# M169X.net
KiCad netlist of a schematic drawn in EAGLE
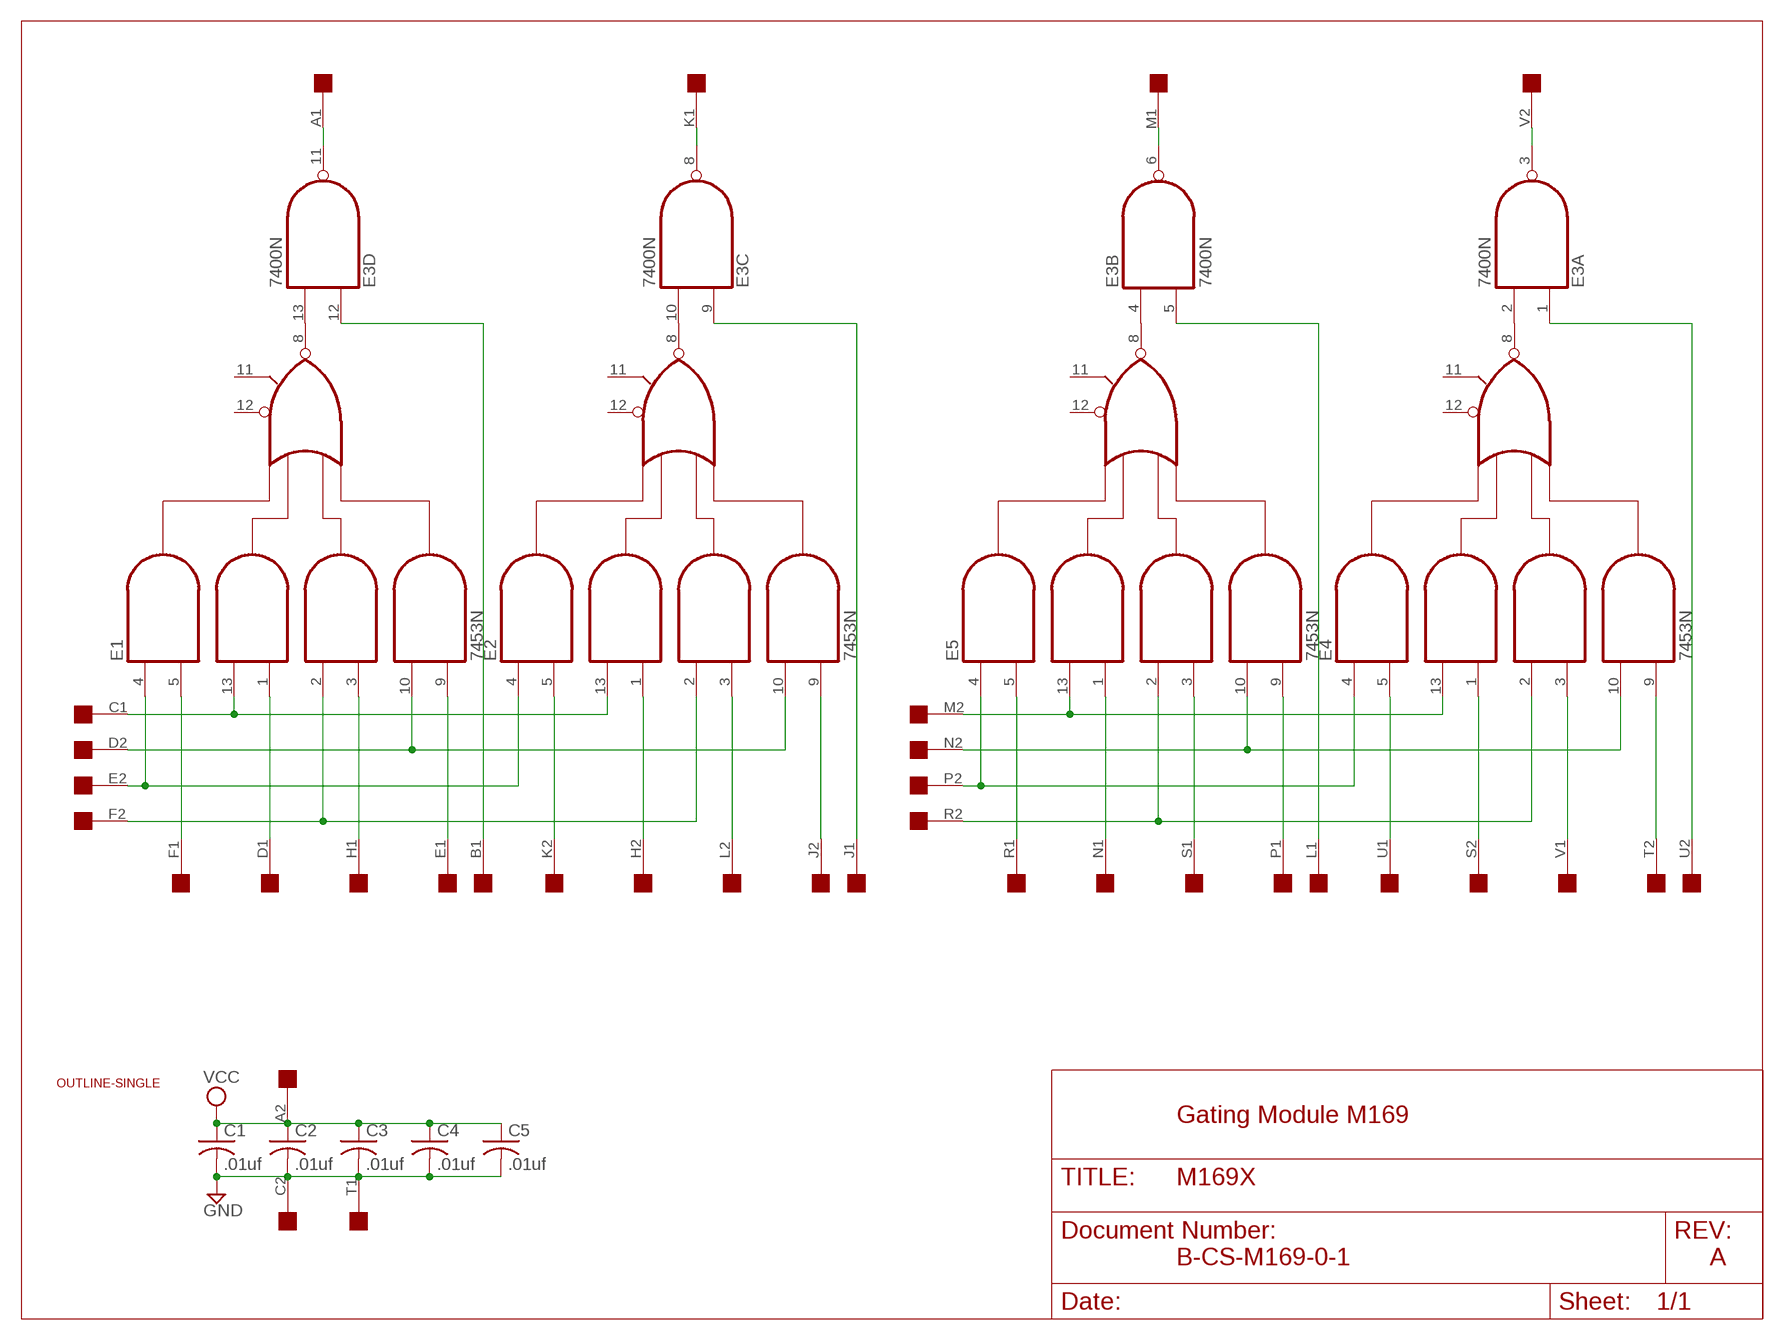
[diagram p0: schematic, sheet 1]

(export (version "E")
  (design (tool "Eeschema 10.0.6"))
  (components
    (comp (ref "C1")
      (value ".01uf")
      (footprint "eagle-import:C050-025X075")
      (libsource (lib "eagle-import") (part "C-US050-025X075"))
    )
    (comp (ref "C2")
      (value ".01uf")
      (footprint "eagle-import:C050-025X075")
      (libsource (lib "eagle-import") (part "C-US050-025X075"))
    )
    (comp (ref "C3")
      (value ".01uf")
      (footprint "eagle-import:C050-025X075")
      (libsource (lib "eagle-import") (part "C-US050-025X075"))
    )
    (comp (ref "C4")
      (value ".01uf")
      (footprint "eagle-import:C050-025X075")
      (libsource (lib "eagle-import") (part "C-US050-025X075"))
    )
    (comp (ref "C5")
      (value ".01uf")
      (footprint "eagle-import:C050-025X075")
      (libsource (lib "eagle-import") (part "C-US050-025X075"))
    )
    (comp (ref "E1")
      (value "7453N")
      (footprint "eagle-import:DIL14")
      (libsource (lib "eagle-import") (part "7453N"))
    )
    (comp (ref "E2")
      (value "7453N")
      (footprint "eagle-import:DIL14")
      (libsource (lib "eagle-import") (part "7453N"))
    )
    (comp (ref "E3")
      (value "7400N")
      (footprint "eagle-import:DIL14")
      (libsource (lib "eagle-import") (part "7400N"))
    )
    (comp (ref "E4")
      (value "7453N")
      (footprint "eagle-import:DIL14")
      (libsource (lib "eagle-import") (part "7453N"))
    )
    (comp (ref "E5")
      (value "7453N")
      (footprint "eagle-import:DIL14")
      (libsource (lib "eagle-import") (part "7453N"))
    )
    (comp (ref "U$1")
      (value "OUTLINE-SINGLE")
      (footprint "eagle-import:SINGLE")
      (libsource (lib "eagle-import") (part "OUTLINE-SINGLE"))
    )
    (comp (ref "U$2")
      (value "EDGE-2CONNECTOR")
      (footprint "eagle-import:EDGE-CON2")
      (libsource (lib "eagle-import") (part "EDGE-2CONNECTOR"))
    )
  )
  (nets
    (net (code "1") (name "GND") (class "Default")
      (node (ref "C1") (pin "2") (pinfunction "2_2") (pintype "passive"))
      (node (ref "C2") (pin "2") (pinfunction "2_2") (pintype "passive"))
      (node (ref "C3") (pin "2") (pinfunction "2_2") (pintype "passive"))
      (node (ref "C4") (pin "2") (pinfunction "2_2") (pintype "passive"))
      (node (ref "C5") (pin "2") (pinfunction "2_2") (pintype "passive"))
      (node (ref "U$2") (pin "C2") (pinfunction "1_C2") (pintype "bidirectional"))
      (node (ref "U$2") (pin "T1") (pinfunction "1_T1") (pintype "bidirectional"))
    )
    (net (code "2") (name "Net-(E1A-I1)") (class "Default")
      (node (ref "E1") (pin "4") (pinfunction "I1_4") (pintype "input"))
      (node (ref "E2") (pin "4") (pinfunction "I1_4") (pintype "input"))
      (node (ref "U$2") (pin "E2") (pinfunction "1_E2") (pintype "bidirectional"))
    )
    (net (code "3") (name "Net-(E1A-I2)") (class "Default")
      (node (ref "E1") (pin "5") (pinfunction "I2_5") (pintype "input"))
      (node (ref "U$2") (pin "F1") (pinfunction "1_F1") (pintype "bidirectional"))
    )
    (net (code "4") (name "Net-(E1A-I3)") (class "Default")
      (node (ref "E1") (pin "13") (pinfunction "I3_13") (pintype "input"))
      (node (ref "E2") (pin "13") (pinfunction "I3_13") (pintype "input"))
      (node (ref "U$2") (pin "C1") (pinfunction "1_C1") (pintype "bidirectional"))
    )
    (net (code "5") (name "Net-(E1A-I4)") (class "Default")
      (node (ref "E1") (pin "1") (pinfunction "I4_1") (pintype "input"))
      (node (ref "U$2") (pin "D1") (pinfunction "1_D1") (pintype "bidirectional"))
    )
    (net (code "6") (name "Net-(E1A-I5)") (class "Default")
      (node (ref "E1") (pin "2") (pinfunction "I5_2") (pintype "input"))
      (node (ref "E2") (pin "2") (pinfunction "I5_2") (pintype "input"))
      (node (ref "U$2") (pin "F2") (pinfunction "1_F2") (pintype "bidirectional"))
    )
    (net (code "7") (name "Net-(E1A-I6)") (class "Default")
      (node (ref "E1") (pin "3") (pinfunction "I6_3") (pintype "input"))
      (node (ref "U$2") (pin "H1") (pinfunction "1_H1") (pintype "bidirectional"))
    )
    (net (code "8") (name "Net-(E1A-I7)") (class "Default")
      (node (ref "E1") (pin "10") (pinfunction "I7_10") (pintype "input"))
      (node (ref "E2") (pin "10") (pinfunction "I7_10") (pintype "input"))
      (node (ref "U$2") (pin "D2") (pinfunction "1_D2") (pintype "bidirectional"))
    )
    (net (code "9") (name "Net-(E1A-I8)") (class "Default")
      (node (ref "E1") (pin "9") (pinfunction "I8_9") (pintype "input"))
      (node (ref "U$2") (pin "E1") (pinfunction "1_E1") (pintype "bidirectional"))
    )
    (net (code "10") (name "Net-(E1A-O)") (class "Default")
      (node (ref "E1") (pin "8") (pinfunction "O_8") (pintype "output"))
      (node (ref "E3") (pin "13") (pinfunction "I1_13") (pintype "input"))
    )
    (net (code "11") (name "Net-(E2A-I2)") (class "Default")
      (node (ref "E2") (pin "5") (pinfunction "I2_5") (pintype "input"))
      (node (ref "U$2") (pin "K2") (pinfunction "1_K2") (pintype "bidirectional"))
    )
    (net (code "12") (name "Net-(E2A-I4)") (class "Default")
      (node (ref "E2") (pin "1") (pinfunction "I4_1") (pintype "input"))
      (node (ref "U$2") (pin "H2") (pinfunction "1_H2") (pintype "bidirectional"))
    )
    (net (code "13") (name "Net-(E2A-I6)") (class "Default")
      (node (ref "E2") (pin "3") (pinfunction "I6_3") (pintype "input"))
      (node (ref "U$2") (pin "L2") (pinfunction "1_L2") (pintype "bidirectional"))
    )
    (net (code "14") (name "Net-(E2A-I8)") (class "Default")
      (node (ref "E2") (pin "9") (pinfunction "I8_9") (pintype "input"))
      (node (ref "U$2") (pin "J2") (pinfunction "1_J2") (pintype "bidirectional"))
    )
    (net (code "15") (name "Net-(E2A-O)") (class "Default")
      (node (ref "E2") (pin "8") (pinfunction "O_8") (pintype "output"))
      (node (ref "E3") (pin "10") (pinfunction "I1_10") (pintype "input"))
    )
    (net (code "16") (name "Net-(E3A-I0)") (class "Default")
      (node (ref "E3") (pin "1") (pinfunction "I0_1") (pintype "input"))
      (node (ref "U$2") (pin "U2") (pinfunction "1_U2") (pintype "bidirectional"))
    )
    (net (code "17") (name "Net-(E3A-I1)") (class "Default")
      (node (ref "E3") (pin "2") (pinfunction "I1_2") (pintype "input"))
      (node (ref "E4") (pin "8") (pinfunction "O_8") (pintype "output"))
    )
    (net (code "18") (name "Net-(E3A-O)") (class "Default")
      (node (ref "E3") (pin "3") (pinfunction "O_3") (pintype "output"))
      (node (ref "U$2") (pin "V2") (pinfunction "1_V2") (pintype "bidirectional"))
    )
    (net (code "19") (name "Net-(E3B-I0)") (class "Default")
      (node (ref "E3") (pin "4") (pinfunction "I0_4") (pintype "input"))
      (node (ref "E5") (pin "8") (pinfunction "O_8") (pintype "output"))
    )
    (net (code "20") (name "Net-(E3B-I1)") (class "Default")
      (node (ref "E3") (pin "5") (pinfunction "I1_5") (pintype "input"))
      (node (ref "U$2") (pin "L1") (pinfunction "1_L1") (pintype "bidirectional"))
    )
    (net (code "21") (name "Net-(E3B-O)") (class "Default")
      (node (ref "E3") (pin "6") (pinfunction "O_6") (pintype "output"))
      (node (ref "U$2") (pin "M1") (pinfunction "1_M1") (pintype "bidirectional"))
    )
    (net (code "22") (name "Net-(E3C-I0)") (class "Default")
      (node (ref "E3") (pin "9") (pinfunction "I0_9") (pintype "input"))
      (node (ref "U$2") (pin "J1") (pinfunction "1_J1") (pintype "bidirectional"))
    )
    (net (code "23") (name "Net-(E3C-O)") (class "Default")
      (node (ref "E3") (pin "8") (pinfunction "O_8") (pintype "output"))
      (node (ref "U$2") (pin "K1") (pinfunction "1_K1") (pintype "bidirectional"))
    )
    (net (code "24") (name "Net-(E3D-I0)") (class "Default")
      (node (ref "E3") (pin "12") (pinfunction "I0_12") (pintype "input"))
      (node (ref "U$2") (pin "B1") (pinfunction "1_B1") (pintype "bidirectional"))
    )
    (net (code "25") (name "Net-(E3D-O)") (class "Default")
      (node (ref "E3") (pin "11") (pinfunction "O_11") (pintype "output"))
      (node (ref "U$2") (pin "A1") (pinfunction "1_A1") (pintype "bidirectional"))
    )
    (net (code "26") (name "Net-(E4A-I1)") (class "Default")
      (node (ref "E4") (pin "4") (pinfunction "I1_4") (pintype "input"))
      (node (ref "E5") (pin "4") (pinfunction "I1_4") (pintype "input"))
      (node (ref "U$2") (pin "P2") (pinfunction "1_P2") (pintype "bidirectional"))
    )
    (net (code "27") (name "Net-(E4A-I2)") (class "Default")
      (node (ref "E4") (pin "5") (pinfunction "I2_5") (pintype "input"))
      (node (ref "U$2") (pin "U1") (pinfunction "1_U1") (pintype "bidirectional"))
    )
    (net (code "28") (name "Net-(E4A-I3)") (class "Default")
      (node (ref "E4") (pin "13") (pinfunction "I3_13") (pintype "input"))
      (node (ref "E5") (pin "13") (pinfunction "I3_13") (pintype "input"))
      (node (ref "U$2") (pin "M2") (pinfunction "1_M2") (pintype "bidirectional"))
    )
    (net (code "29") (name "Net-(E4A-I4)") (class "Default")
      (node (ref "E4") (pin "1") (pinfunction "I4_1") (pintype "input"))
      (node (ref "U$2") (pin "S2") (pinfunction "1_S2") (pintype "bidirectional"))
    )
    (net (code "30") (name "Net-(E4A-I5)") (class "Default")
      (node (ref "E4") (pin "2") (pinfunction "I5_2") (pintype "input"))
      (node (ref "E5") (pin "2") (pinfunction "I5_2") (pintype "input"))
      (node (ref "U$2") (pin "R2") (pinfunction "1_R2") (pintype "bidirectional"))
    )
    (net (code "31") (name "Net-(E4A-I6)") (class "Default")
      (node (ref "E4") (pin "3") (pinfunction "I6_3") (pintype "input"))
      (node (ref "U$2") (pin "V1") (pinfunction "1_V1") (pintype "bidirectional"))
    )
    (net (code "32") (name "Net-(E4A-I7)") (class "Default")
      (node (ref "E4") (pin "10") (pinfunction "I7_10") (pintype "input"))
      (node (ref "E5") (pin "10") (pinfunction "I7_10") (pintype "input"))
      (node (ref "U$2") (pin "N2") (pinfunction "1_N2") (pintype "bidirectional"))
    )
    (net (code "33") (name "Net-(E4A-I8)") (class "Default")
      (node (ref "E4") (pin "9") (pinfunction "I8_9") (pintype "input"))
      (node (ref "U$2") (pin "T2") (pinfunction "1_T2") (pintype "bidirectional"))
    )
    (net (code "34") (name "Net-(E5A-I2)") (class "Default")
      (node (ref "E5") (pin "5") (pinfunction "I2_5") (pintype "input"))
      (node (ref "U$2") (pin "R1") (pinfunction "1_R1") (pintype "bidirectional"))
    )
    (net (code "35") (name "Net-(E5A-I4)") (class "Default")
      (node (ref "E5") (pin "1") (pinfunction "I4_1") (pintype "input"))
      (node (ref "U$2") (pin "N1") (pinfunction "1_N1") (pintype "bidirectional"))
    )
    (net (code "36") (name "Net-(E5A-I6)") (class "Default")
      (node (ref "E5") (pin "3") (pinfunction "I6_3") (pintype "input"))
      (node (ref "U$2") (pin "S1") (pinfunction "1_S1") (pintype "bidirectional"))
    )
    (net (code "37") (name "Net-(E5A-I8)") (class "Default")
      (node (ref "E5") (pin "9") (pinfunction "I8_9") (pintype "input"))
      (node (ref "U$2") (pin "P1") (pinfunction "1_P1") (pintype "bidirectional"))
    )
    (net (code "38") (name "VCC") (class "Default")
      (node (ref "C1") (pin "1") (pinfunction "1_1") (pintype "passive"))
      (node (ref "C2") (pin "1") (pinfunction "1_1") (pintype "passive"))
      (node (ref "C3") (pin "1") (pinfunction "1_1") (pintype "passive"))
      (node (ref "C4") (pin "1") (pinfunction "1_1") (pintype "passive"))
      (node (ref "C5") (pin "1") (pinfunction "1_1") (pintype "passive"))
      (node (ref "U$2") (pin "A2") (pinfunction "1_A2") (pintype "bidirectional"))
    )
    (net (code "39") (name "unconnected-(E1A-I9-Pad12)") (class "Default")
      (node (ref "E1") (pin "12") (pinfunction "I9_12") (pintype "passive"))
    )
    (net (code "40") (name "unconnected-(E1A-I10-Pad11)") (class "Default")
      (node (ref "E1") (pin "11") (pinfunction "I10_11") (pintype "passive"))
    )
    (net (code "41") (name "unconnected-(E2A-I9-Pad12)") (class "Default")
      (node (ref "E2") (pin "12") (pinfunction "I9_12") (pintype "passive"))
    )
    (net (code "42") (name "unconnected-(E2A-I10-Pad11)") (class "Default")
      (node (ref "E2") (pin "11") (pinfunction "I10_11") (pintype "passive"))
    )
    (net (code "43") (name "unconnected-(E4A-I9-Pad12)") (class "Default")
      (node (ref "E4") (pin "12") (pinfunction "I9_12") (pintype "passive"))
    )
    (net (code "44") (name "unconnected-(E4A-I10-Pad11)") (class "Default")
      (node (ref "E4") (pin "11") (pinfunction "I10_11") (pintype "passive"))
    )
    (net (code "45") (name "unconnected-(E5A-I9-Pad12)") (class "Default")
      (node (ref "E5") (pin "12") (pinfunction "I9_12") (pintype "passive"))
    )
    (net (code "46") (name "unconnected-(E5A-I10-Pad11)") (class "Default")
      (node (ref "E5") (pin "11") (pinfunction "I10_11") (pintype "passive"))
    )
  )
)
